# main.net
KiCad netlist of a schematic drawn in Altium Designer
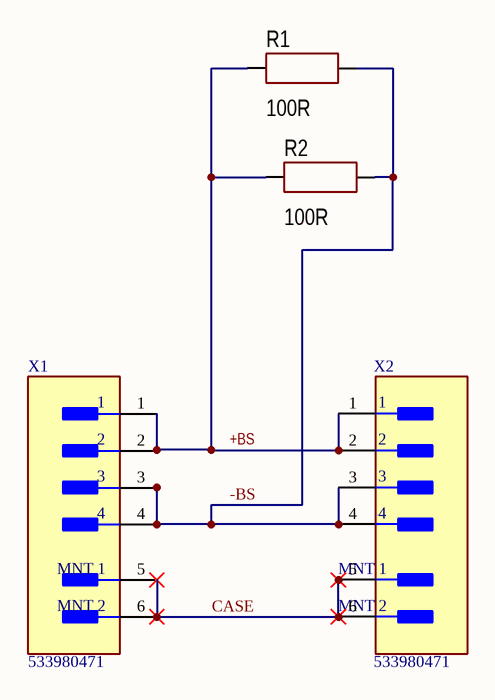
[diagram p0: main.SchDoc]

(export (version "E")
  (design (tool "Eeschema 10.0.6"))
  (components
    (comp (ref "R1")
      (value "100R")
      (footprint "RES: 0805")
      (fields
        (field (name "MANUFACTURER") "Yageo")
        (field (name "PARTNUMBER") "RC0805JR-07100RL")
        (field (name "VALUEMANUFACTURERPARTNUMBER") "Resistor film, 100R, , 0805, 0.125W, -55...+125°C")
      )
      (libsource (lib "resistor") (part "Resistor_0805"))
    )
    (comp (ref "R2")
      (value "100R")
      (footprint "RES: 0805")
      (fields
        (field (name "MANUFACTURER") "Yageo")
        (field (name "PARTNUMBER") "RC0805JR-07100RL")
        (field (name "VALUEMANUFACTURERPARTNUMBER") "Resistor film, 100R, , 0805, 0.125W, -55...+125°C")
      )
      (libsource (lib "resistor") (part "Resistor_0805"))
    )
    (comp (ref "X1")
      (value "533980471")
      (footprint "FP-533980471-MFG")
      (description "CONN HEADER SMD 4POS 1.25MM")
      (fields
        (field (name "OCTOPART") "https://octopart.com/53398-0471-molex-655296")
        (field (name "MANUFACTURER") "Molex")
      )
      (libsource (lib "Altium Content Vault") (part "3b6f738a5616415d78381ad43816e4a"))
    )
    (comp (ref "X2")
      (value "533980471")
      (footprint "FP-533980471-MFG")
      (description "CONN HEADER SMD 4POS 1.25MM")
      (fields
        (field (name "OCTOPART") "https://octopart.com/53398-0471-molex-655296")
        (field (name "MANUFACTURER") "Molex")
      )
      (libsource (lib "") (part "3b6f738a5616415d78381ad43816e4a_1"))
    )
  )
  (nets
    (net (code "2") (name "/+BS") (class "Default")
      (node (ref "R1") (pin "1") (pinfunction "1_1") (pintype "passive"))
      (node (ref "R2") (pin "1") (pinfunction "1_1") (pintype "passive"))
      (node (ref "X1") (pin "1") (pinfunction "1_1") (pintype "passive"))
      (node (ref "X1") (pin "2") (pinfunction "2_2") (pintype "passive"))
      (node (ref "X2") (pin "1") (pinfunction "1_1") (pintype "passive"))
      (node (ref "X2") (pin "2") (pinfunction "2_2") (pintype "passive"))
    )
    (net (code "3") (name "/-BS") (class "Default")
      (node (ref "R1") (pin "2") (pinfunction "2_2") (pintype "passive"))
      (node (ref "R2") (pin "2") (pinfunction "2_2") (pintype "passive"))
      (node (ref "X1") (pin "3") (pinfunction "3_3") (pintype "passive"))
      (node (ref "X1") (pin "4") (pinfunction "4_4") (pintype "passive"))
      (node (ref "X2") (pin "3") (pinfunction "3_3") (pintype "passive"))
      (node (ref "X2") (pin "4") (pinfunction "4_4") (pintype "passive"))
    )
    (net (code "4") (name "/CASE") (class "Default")
      (node (ref "X1") (pin "5") (pinfunction "MNT_1_5") (pintype "passive"))
      (node (ref "X1") (pin "6") (pinfunction "MNT_2_6") (pintype "passive"))
      (node (ref "X2") (pin "5") (pinfunction "MNT_1_5") (pintype "passive"))
      (node (ref "X2") (pin "6") (pinfunction "MNT_2_6") (pintype "passive"))
    )
  )
)
